# SCS_schematics.net
KiCad netlist of a schematic drawn in EAGLE
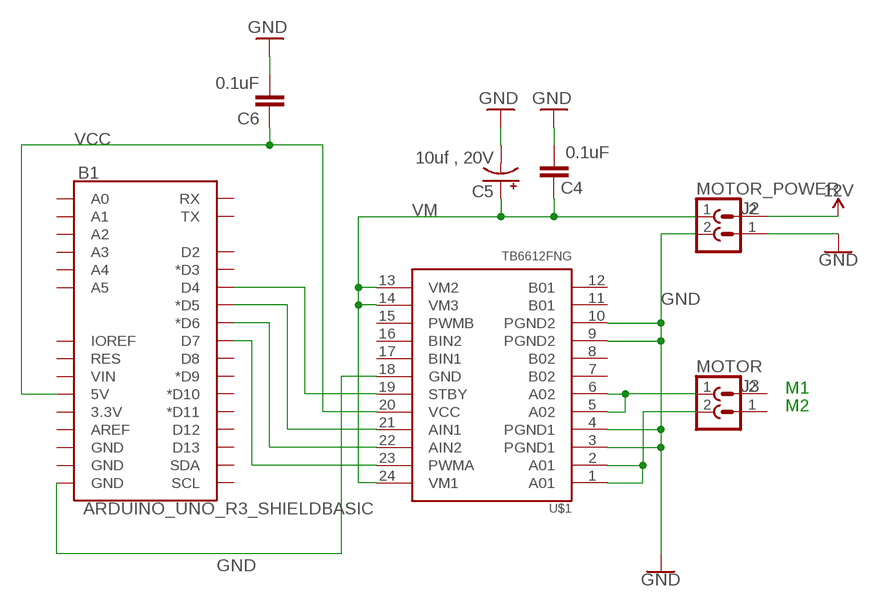
[diagram p0: schematic, sheet 1]

(export (version "E")
  (design (tool "Eeschema 10.0.6"))
  (components
    (comp (ref "B1")
      (value "ARDUINO_UNO_R3_SHIELDBASIC")
      (footprint "eagle-import:UNO_R3_SHIELD")
      (libsource (lib "eagle-import") (part "ARDUINO_UNO_R3_SHIELDBASIC"))
    )
    (comp (ref "C4")
      (value "0.1uF")
      (footprint "eagle-import:0402-CAP")
      (libsource (lib "eagle-import") (part "CAP0402-CAP"))
    )
    (comp (ref "C5")
      (value "10uf , 20V")
      (footprint "eagle-import:EIA3528")
      (libsource (lib "eagle-import") (part "CAP_POL3528"))
    )
    (comp (ref "C6")
      (value "0.1uF")
      (footprint "eagle-import:0402-CAP")
      (libsource (lib "eagle-import") (part "CAP0402-CAP"))
    )
    (comp (ref "J2")
      (value "691217910002")
      (footprint "eagle-import:691217910002")
      (libsource (lib "eagle-import") (part "691217910002"))
    )
    (comp (ref "J3")
      (value "691217910002")
      (footprint "eagle-import:691217910002")
      (libsource (lib "eagle-import") (part "691217910002"))
    )
    (comp (ref "MOTOR")
      (value "CONN_02JST-PTH-2")
      (footprint "eagle-import:JST-2-PTH")
      (libsource (lib "eagle-import") (part "CONN_02JST-PTH-2"))
    )
    (comp (ref "MOTOR_POWER")
      (value "CONN_02JST-PTH-2")
      (footprint "eagle-import:JST-2-PTH")
      (fields (field (name "PROD_ID") "12V") (field (name "SKU") "GND"))
      (libsource (lib "eagle-import") (part "CONN_02JST-PTH-2"))
    )
    (comp (ref "U$1")
      (value "TB6612FNG")
      (footprint "eagle-import:SSOP24")
      (libsource (lib "eagle-import") (part "TB6612FNG"))
    )
  )
  (nets
    (net (code "1") (name "/VCC") (class "Default")
      (node (ref "B1") (pin "5V") (pinfunction "5V_5V") (pintype "bidirectional"))
      (node (ref "C6") (pin "1") (pinfunction "1_1") (pintype "passive"))
      (node (ref "U$1") (pin "20") (pinfunction "VCC_20") (pintype "bidirectional"))
    )
    (net (code "2") (name "/VM") (class "Default")
      (node (ref "C4") (pin "1") (pinfunction "1_1") (pintype "passive"))
      (node (ref "C5") (pin "A") (pinfunction "+_A") (pintype "passive"))
      (node (ref "J2") (pin "1") (pinfunction "1_1") (pintype "passive"))
      (node (ref "U$1") (pin "13") (pinfunction "VM2_13") (pintype "bidirectional"))
      (node (ref "U$1") (pin "14") (pinfunction "VM3_14") (pintype "bidirectional"))
      (node (ref "U$1") (pin "24") (pinfunction "VM1_24") (pintype "bidirectional"))
    )
    (net (code "3") (name "12V") (class "Default")
      (node (ref "MOTOR_POWER") (pin "2") (pinfunction "2_2") (pintype "passive"))
    )
    (net (code "4") (name "GND") (class "Default")
      (node (ref "B1") (pin "GND@0") (pinfunction "GND_GND@0") (pintype "bidirectional"))
      (node (ref "C4") (pin "2") (pinfunction "2_2") (pintype "passive"))
      (node (ref "C5") (pin "C") (pinfunction "-_C") (pintype "passive"))
      (node (ref "C6") (pin "2") (pinfunction "2_2") (pintype "passive"))
      (node (ref "J2") (pin "2") (pinfunction "2_2") (pintype "passive"))
      (node (ref "MOTOR_POWER") (pin "1") (pinfunction "1_1") (pintype "passive"))
      (node (ref "U$1") (pin "10") (pinfunction "PGND2_10") (pintype "bidirectional"))
      (node (ref "U$1") (pin "18") (pinfunction "GND_18") (pintype "bidirectional"))
      (node (ref "U$1") (pin "3") (pinfunction "PGND1_3") (pintype "bidirectional"))
      (node (ref "U$1") (pin "4") (pinfunction "PGND1_4") (pintype "bidirectional"))
      (node (ref "U$1") (pin "9") (pinfunction "PGND2_9") (pintype "bidirectional"))
    )
    (net (code "5") (name "Net-(B1-*D5)") (class "Default")
      (node (ref "B1") (pin "D5") (pinfunction "*D5_D5") (pintype "bidirectional"))
      (node (ref "U$1") (pin "21") (pinfunction "AIN1_21") (pintype "bidirectional"))
    )
    (net (code "6") (name "Net-(B1-*D6)") (class "Default")
      (node (ref "B1") (pin "D6") (pinfunction "*D6_D6") (pintype "bidirectional"))
      (node (ref "U$1") (pin "22") (pinfunction "AIN2_22") (pintype "bidirectional"))
    )
    (net (code "7") (name "Net-(J3-Pad1)") (class "Default")
      (node (ref "J3") (pin "1") (pinfunction "1_1") (pintype "passive"))
      (node (ref "U$1") (pin "5") (pinfunction "A02_5") (pintype "bidirectional"))
      (node (ref "U$1") (pin "6") (pinfunction "A02_6") (pintype "bidirectional"))
    )
    (net (code "8") (name "Net-(J3-Pad2)") (class "Default")
      (node (ref "J3") (pin "2") (pinfunction "2_2") (pintype "passive"))
      (node (ref "U$1") (pin "1") (pinfunction "A01_1") (pintype "bidirectional"))
      (node (ref "U$1") (pin "2") (pinfunction "A01_2") (pintype "bidirectional"))
    )
    (net (code "9") (name "Net-(U$1-PWMA)") (class "Default")
      (node (ref "B1") (pin "D7") (pinfunction "D7_D7") (pintype "bidirectional"))
      (node (ref "U$1") (pin "23") (pinfunction "PWMA_23") (pintype "bidirectional"))
    )
    (net (code "10") (name "Net-(U$1-STBY)") (class "Default")
      (node (ref "B1") (pin "D4") (pinfunction "D4_D4") (pintype "bidirectional"))
      (node (ref "U$1") (pin "19") (pinfunction "STBY_19") (pintype "bidirectional"))
    )
    (net (code "11") (name "unconnected-(B1-*D3-PadD3)") (class "Default")
      (node (ref "B1") (pin "D3") (pinfunction "*D3_D3") (pintype "bidirectional"))
    )
    (net (code "12") (name "unconnected-(B1-*D9-PadD9)") (class "Default")
      (node (ref "B1") (pin "D9") (pinfunction "*D9_D9") (pintype "bidirectional"))
    )
    (net (code "13") (name "unconnected-(B1-*D10-PadD10)") (class "Default")
      (node (ref "B1") (pin "D10") (pinfunction "*D10_D10") (pintype "bidirectional"))
    )
    (net (code "14") (name "unconnected-(B1-*D11-PadD11)") (class "Default")
      (node (ref "B1") (pin "D11") (pinfunction "*D11_D11") (pintype "bidirectional"))
    )
    (net (code "15") (name "unconnected-(B1-GND-PadGND@1)") (class "Default")
      (node (ref "B1") (pin "GND@1") (pinfunction "GND_GND@1") (pintype "bidirectional"))
    )
    (net (code "16") (name "unconnected-(B1-GND-PadGND@2)") (class "Default")
      (node (ref "B1") (pin "GND@2") (pinfunction "GND_GND@2") (pintype "bidirectional"))
    )
    (net (code "17") (name "unconnected-(B1-Pad3.3V)") (class "Default")
      (node (ref "B1") (pin "3.3V") (pinfunction "3.3V_3.3V") (pintype "bidirectional"))
    )
    (net (code "18") (name "unconnected-(B1-PadA0)") (class "Default")
      (node (ref "B1") (pin "A0") (pinfunction "A0_A0") (pintype "bidirectional"))
    )
    (net (code "19") (name "unconnected-(B1-PadA1)") (class "Default")
      (node (ref "B1") (pin "A1") (pinfunction "A1_A1") (pintype "bidirectional"))
    )
    (net (code "20") (name "unconnected-(B1-PadA2)") (class "Default")
      (node (ref "B1") (pin "A2") (pinfunction "A2_A2") (pintype "bidirectional"))
    )
    (net (code "21") (name "unconnected-(B1-PadA3)") (class "Default")
      (node (ref "B1") (pin "A3") (pinfunction "A3_A3") (pintype "bidirectional"))
    )
    (net (code "22") (name "unconnected-(B1-PadA4)") (class "Default")
      (node (ref "B1") (pin "A4") (pinfunction "A4_A4") (pintype "bidirectional"))
    )
    (net (code "23") (name "unconnected-(B1-PadA5)") (class "Default")
      (node (ref "B1") (pin "A5") (pinfunction "A5_A5") (pintype "bidirectional"))
    )
    (net (code "24") (name "unconnected-(B1-PadAREF)") (class "Default")
      (node (ref "B1") (pin "AREF") (pinfunction "AREF_AREF") (pintype "bidirectional"))
    )
    (net (code "25") (name "unconnected-(B1-PadD2)") (class "Default")
      (node (ref "B1") (pin "D2") (pinfunction "D2_D2") (pintype "bidirectional"))
    )
    (net (code "26") (name "unconnected-(B1-PadD8)") (class "Default")
      (node (ref "B1") (pin "D8") (pinfunction "D8_D8") (pintype "bidirectional"))
    )
    (net (code "27") (name "unconnected-(B1-PadD12)") (class "Default")
      (node (ref "B1") (pin "D12") (pinfunction "D12_D12") (pintype "bidirectional"))
    )
    (net (code "28") (name "unconnected-(B1-PadD13)") (class "Default")
      (node (ref "B1") (pin "D13") (pinfunction "D13_D13") (pintype "bidirectional"))
    )
    (net (code "29") (name "unconnected-(B1-PadIOREF)") (class "Default")
      (node (ref "B1") (pin "IOREF") (pinfunction "IOREF_IOREF") (pintype "bidirectional"))
    )
    (net (code "30") (name "unconnected-(B1-PadRES)") (class "Default")
      (node (ref "B1") (pin "RES") (pinfunction "RES_RES") (pintype "bidirectional"))
    )
    (net (code "31") (name "unconnected-(B1-PadRX)") (class "Default")
      (node (ref "B1") (pin "RX") (pinfunction "RX_RX") (pintype "bidirectional"))
    )
    (net (code "32") (name "unconnected-(B1-PadSCL)") (class "Default")
      (node (ref "B1") (pin "SCL") (pinfunction "SCL_SCL") (pintype "bidirectional"))
    )
    (net (code "33") (name "unconnected-(B1-PadSDA)") (class "Default")
      (node (ref "B1") (pin "SDA") (pinfunction "SDA_SDA") (pintype "bidirectional"))
    )
    (net (code "34") (name "unconnected-(B1-PadTX)") (class "Default")
      (node (ref "B1") (pin "TX") (pinfunction "TX_TX") (pintype "bidirectional"))
    )
    (net (code "35") (name "unconnected-(B1-PadVIN)") (class "Default")
      (node (ref "B1") (pin "VIN") (pinfunction "VIN_VIN") (pintype "bidirectional"))
    )
    (net (code "36") (name "unconnected-(MOTOR-Pad1)") (class "Default")
      (node (ref "MOTOR") (pin "1") (pinfunction "1_1") (pintype "passive"))
    )
    (net (code "37") (name "unconnected-(MOTOR-Pad2)") (class "Default")
      (node (ref "MOTOR") (pin "2") (pinfunction "2_2") (pintype "passive"))
    )
    (net (code "38") (name "unconnected-(U$1-B01-Pad11)") (class "Default")
      (node (ref "U$1") (pin "11") (pinfunction "B01_11") (pintype "bidirectional"))
    )
    (net (code "39") (name "unconnected-(U$1-B01-Pad12)") (class "Default")
      (node (ref "U$1") (pin "12") (pinfunction "B01_12") (pintype "bidirectional"))
    )
    (net (code "40") (name "unconnected-(U$1-B02-Pad7)") (class "Default")
      (node (ref "U$1") (pin "7") (pinfunction "B02_7") (pintype "bidirectional"))
    )
    (net (code "41") (name "unconnected-(U$1-B02-Pad8)") (class "Default")
      (node (ref "U$1") (pin "8") (pinfunction "B02_8") (pintype "bidirectional"))
    )
    (net (code "42") (name "unconnected-(U$1-BIN1-Pad17)") (class "Default")
      (node (ref "U$1") (pin "17") (pinfunction "BIN1_17") (pintype "bidirectional"))
    )
    (net (code "43") (name "unconnected-(U$1-BIN2-Pad16)") (class "Default")
      (node (ref "U$1") (pin "16") (pinfunction "BIN2_16") (pintype "bidirectional"))
    )
    (net (code "44") (name "unconnected-(U$1-PWMB-Pad15)") (class "Default")
      (node (ref "U$1") (pin "15") (pinfunction "PWMB_15") (pintype "bidirectional"))
    )
  )
)
